# Sensor_laser_board_V_1_0.net
KiCad netlist of a schematic drawn in EAGLE
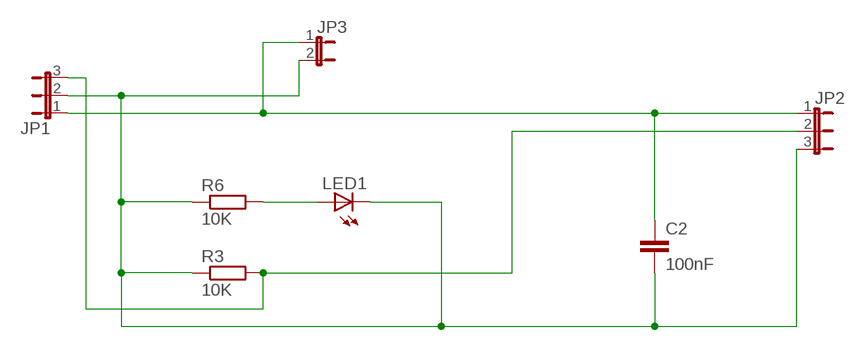
[diagram p0: schematic, sheet 1]

(export (version "E")
  (design (tool "Eeschema 10.0.6"))
  (components
    (comp (ref "C2")
      (value "100nF")
      (footprint "eagle-import:C025_050-025X075")
      (libsource (lib "eagle-import") (part "C-EU025_050-025X075"))
    )
    (comp (ref "JP1")
      (value "JP2E")
      (footprint "eagle-import:JP2")
      (libsource (lib "eagle-import") (part "JP2E"))
    )
    (comp (ref "JP2")
      (value "JP2E")
      (footprint "eagle-import:JP2")
      (libsource (lib "eagle-import") (part "JP2E"))
    )
    (comp (ref "JP3")
      (value "JP1E")
      (footprint "eagle-import:JP1")
      (libsource (lib "eagle-import") (part "JP1E"))
    )
    (comp (ref "LED1")
      (value "LED3MM")
      (footprint "eagle-import:LED3MM")
      (libsource (lib "eagle-import") (part "LED3MM"))
    )
    (comp (ref "R3")
      (value "10K")
      (footprint "eagle-import:0309_10")
      (libsource (lib "eagle-import") (part "R-EU_0309/10"))
    )
    (comp (ref "R6")
      (value "10K")
      (footprint "eagle-import:0309_10")
      (libsource (lib "eagle-import") (part "R-EU_0309/10"))
    )
  )
  (nets
    (net (code "1") (name "Net-(C2-Pad1)") (class "Default")
      (node (ref "C2") (pin "1") (pinfunction "1_1") (pintype "passive"))
      (node (ref "JP1") (pin "1") (pinfunction "1_1") (pintype "passive"))
      (node (ref "JP2") (pin "1") (pinfunction "1_1") (pintype "passive"))
      (node (ref "JP3") (pin "1") (pinfunction "1_1") (pintype "passive"))
    )
    (net (code "2") (name "Net-(JP1-Pad3)") (class "Default")
      (node (ref "JP1") (pin "3") (pinfunction "3_3") (pintype "passive"))
      (node (ref "JP2") (pin "2") (pinfunction "2_2") (pintype "passive"))
      (node (ref "R3") (pin "2") (pinfunction "2_2") (pintype "passive"))
    )
    (net (code "3") (name "Net-(LED1-C)") (class "Default")
      (node (ref "C2") (pin "2") (pinfunction "2_2") (pintype "passive"))
      (node (ref "JP1") (pin "2") (pinfunction "2_2") (pintype "passive"))
      (node (ref "JP2") (pin "3") (pinfunction "3_3") (pintype "passive"))
      (node (ref "JP3") (pin "2") (pinfunction "2_2") (pintype "passive"))
      (node (ref "LED1") (pin "K") (pinfunction "C_K") (pintype "passive"))
      (node (ref "R3") (pin "1") (pinfunction "1_1") (pintype "passive"))
      (node (ref "R6") (pin "1") (pinfunction "1_1") (pintype "passive"))
    )
    (net (code "4") (name "Net-(LED1-PadA)") (class "Default")
      (node (ref "LED1") (pin "A") (pinfunction "A_A") (pintype "passive"))
      (node (ref "R6") (pin "2") (pinfunction "2_2") (pintype "passive"))
    )
  )
)
